# ReButton-ES2.net
KiCad netlist of a schematic drawn in EAGLE
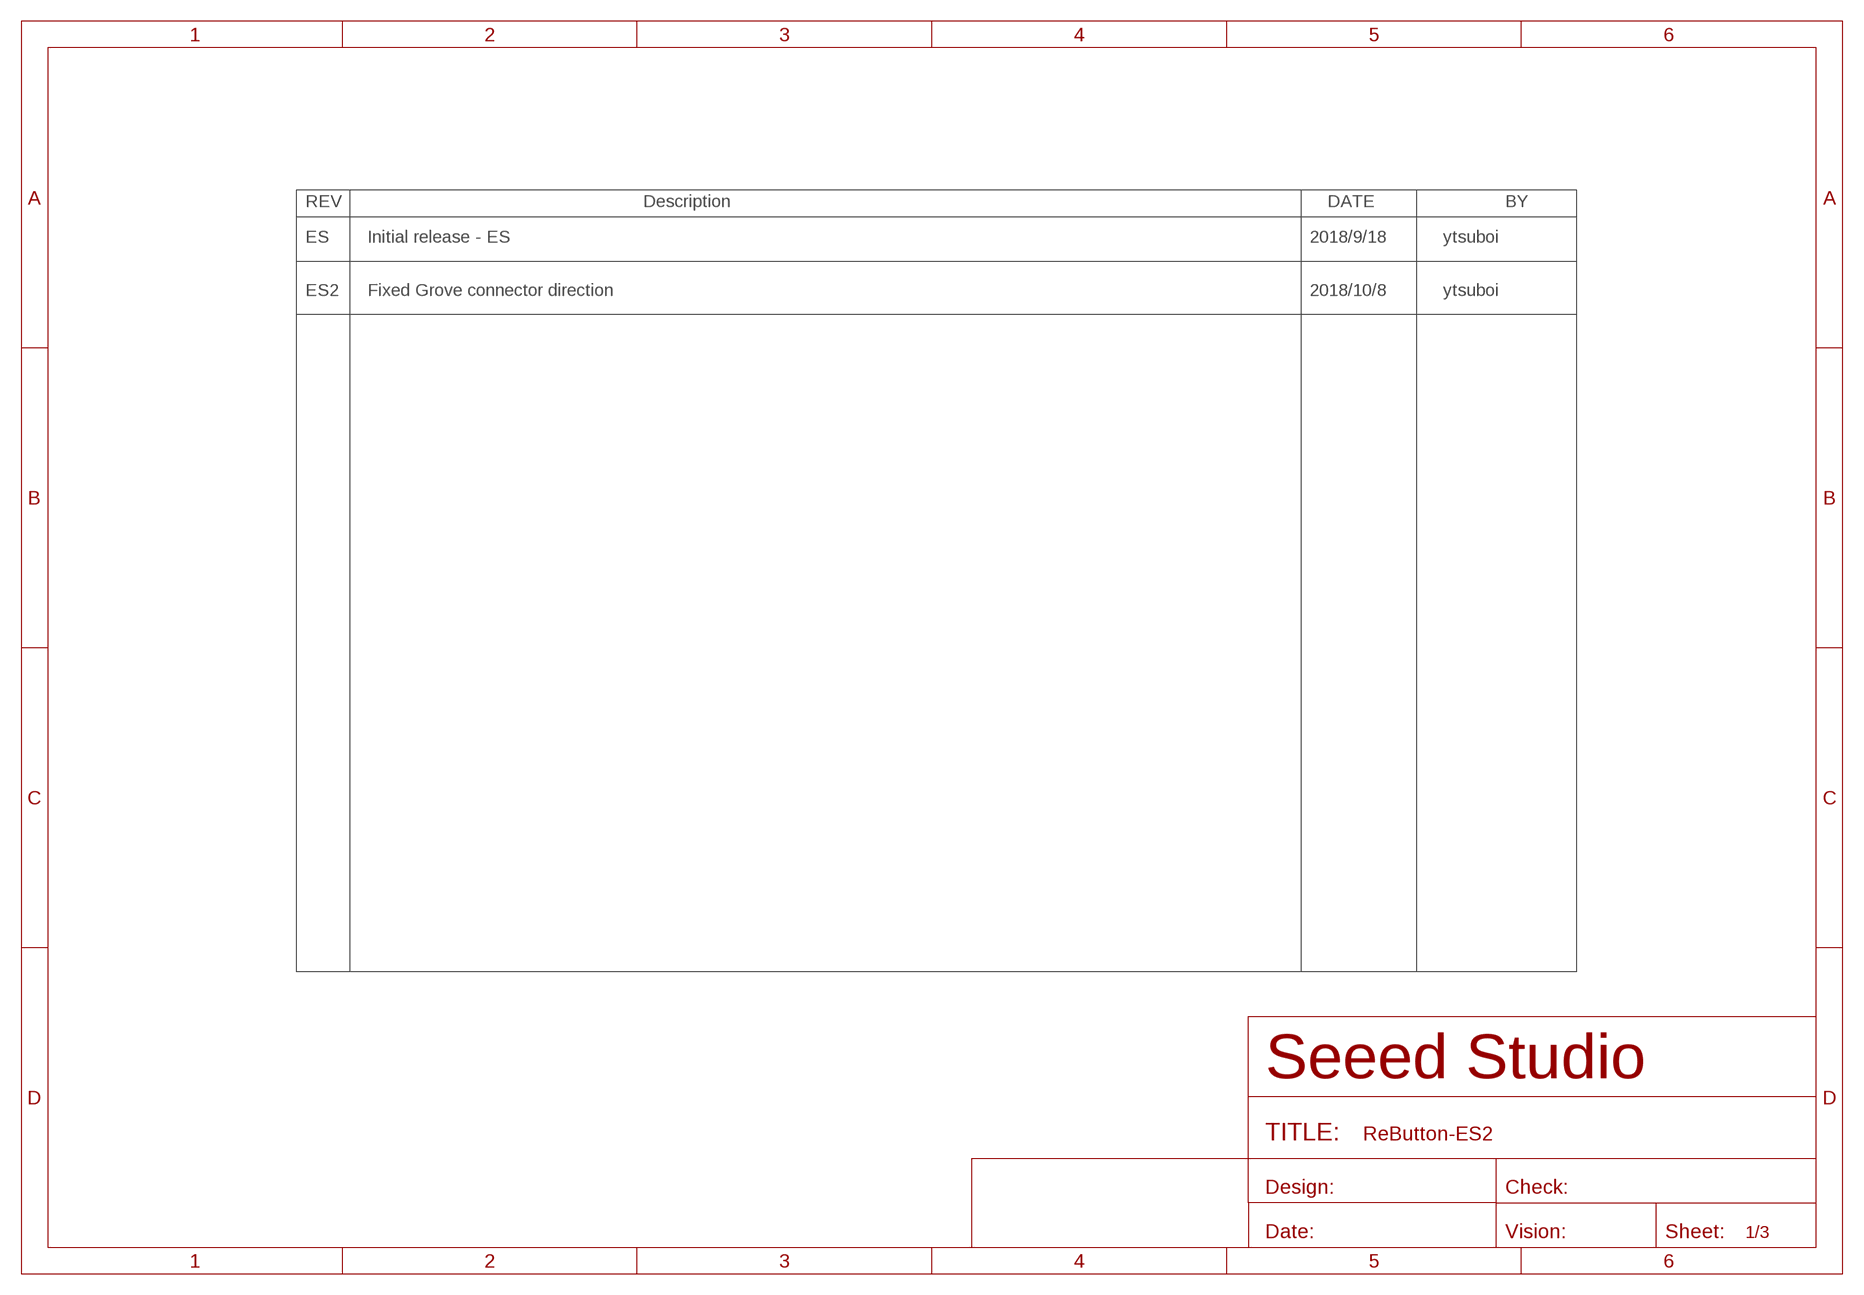
[diagram p0: schematic, sheet 1]
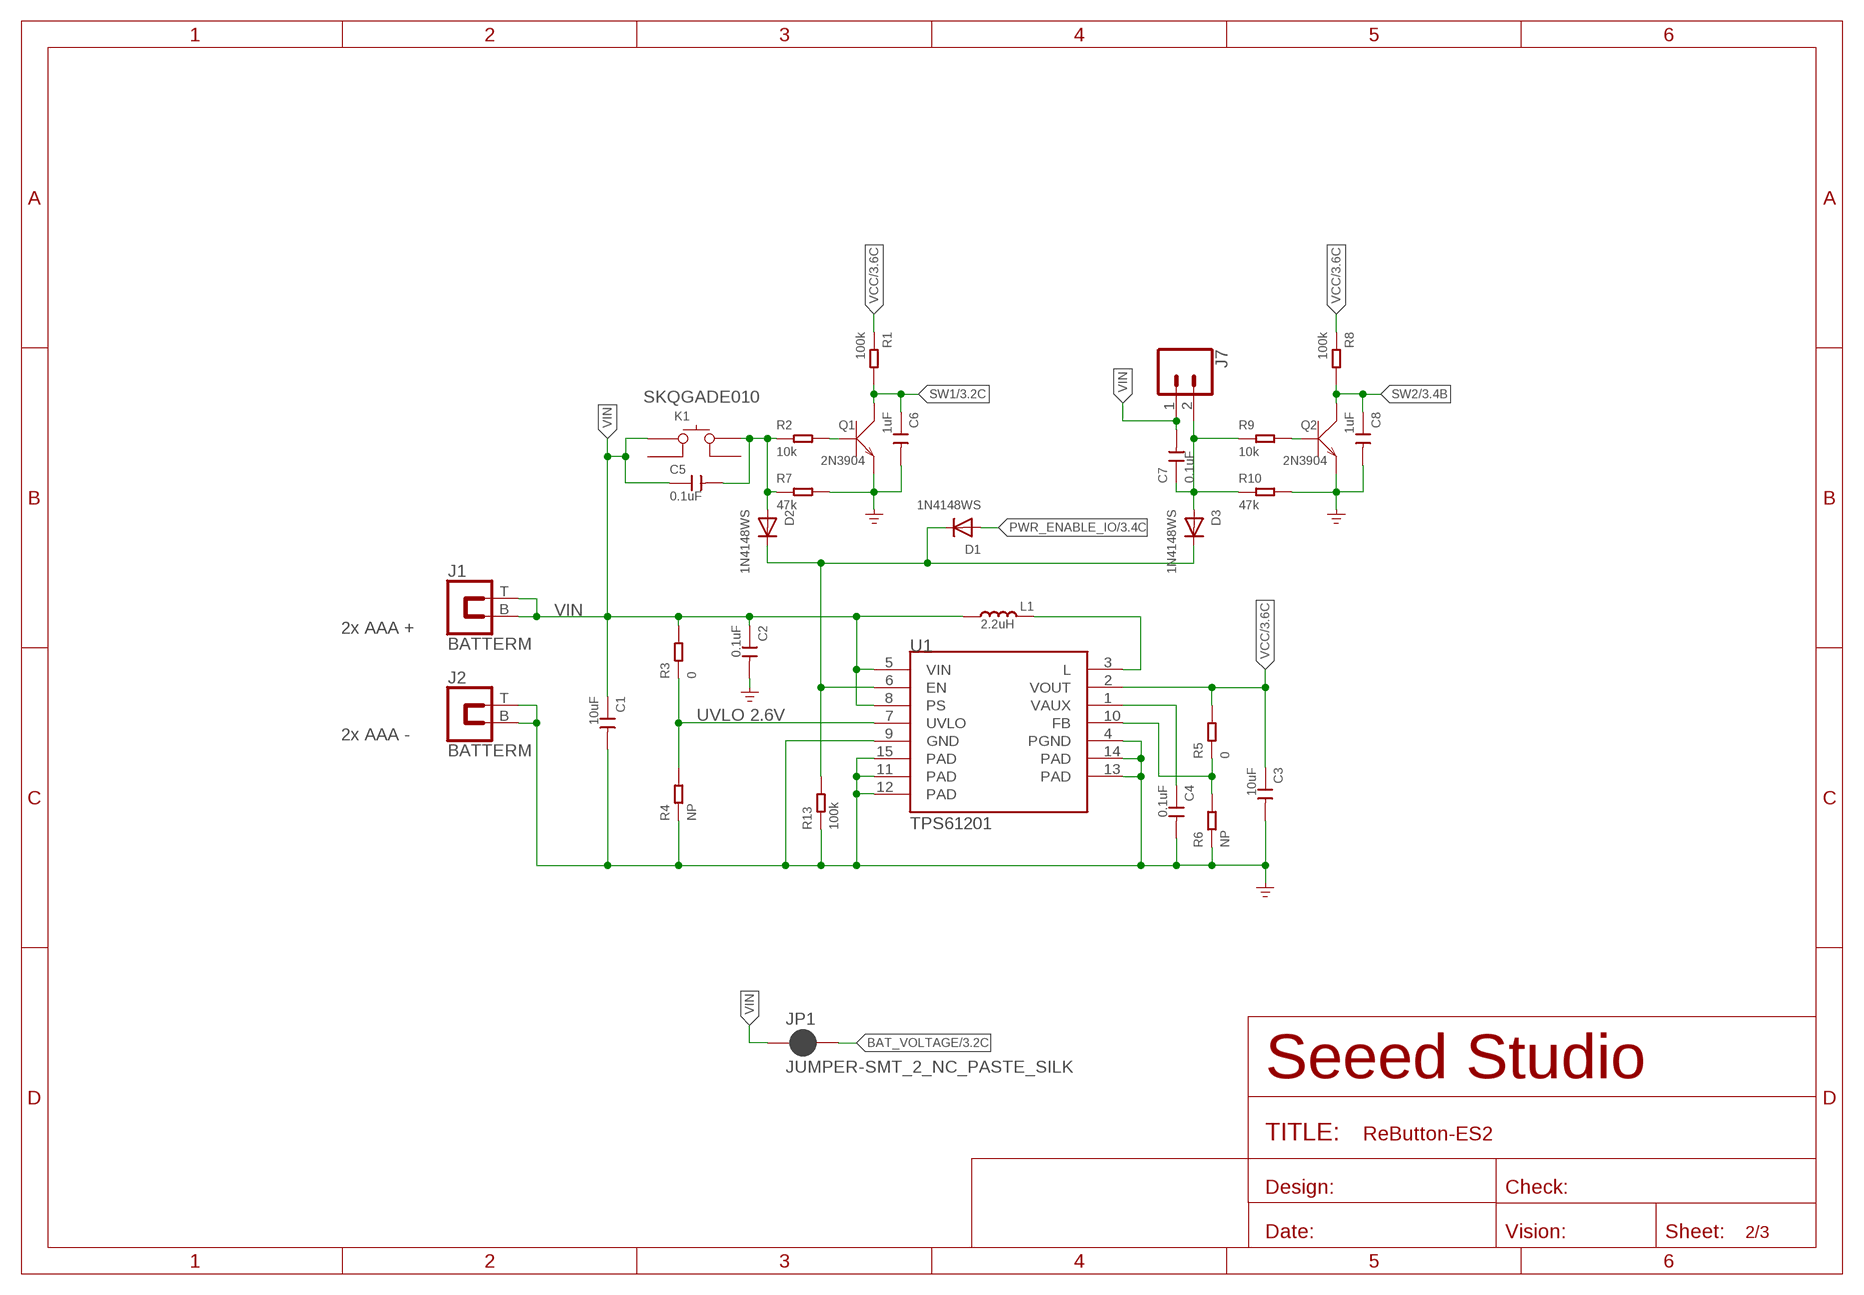
[diagram p1: schematic, sheet 2]
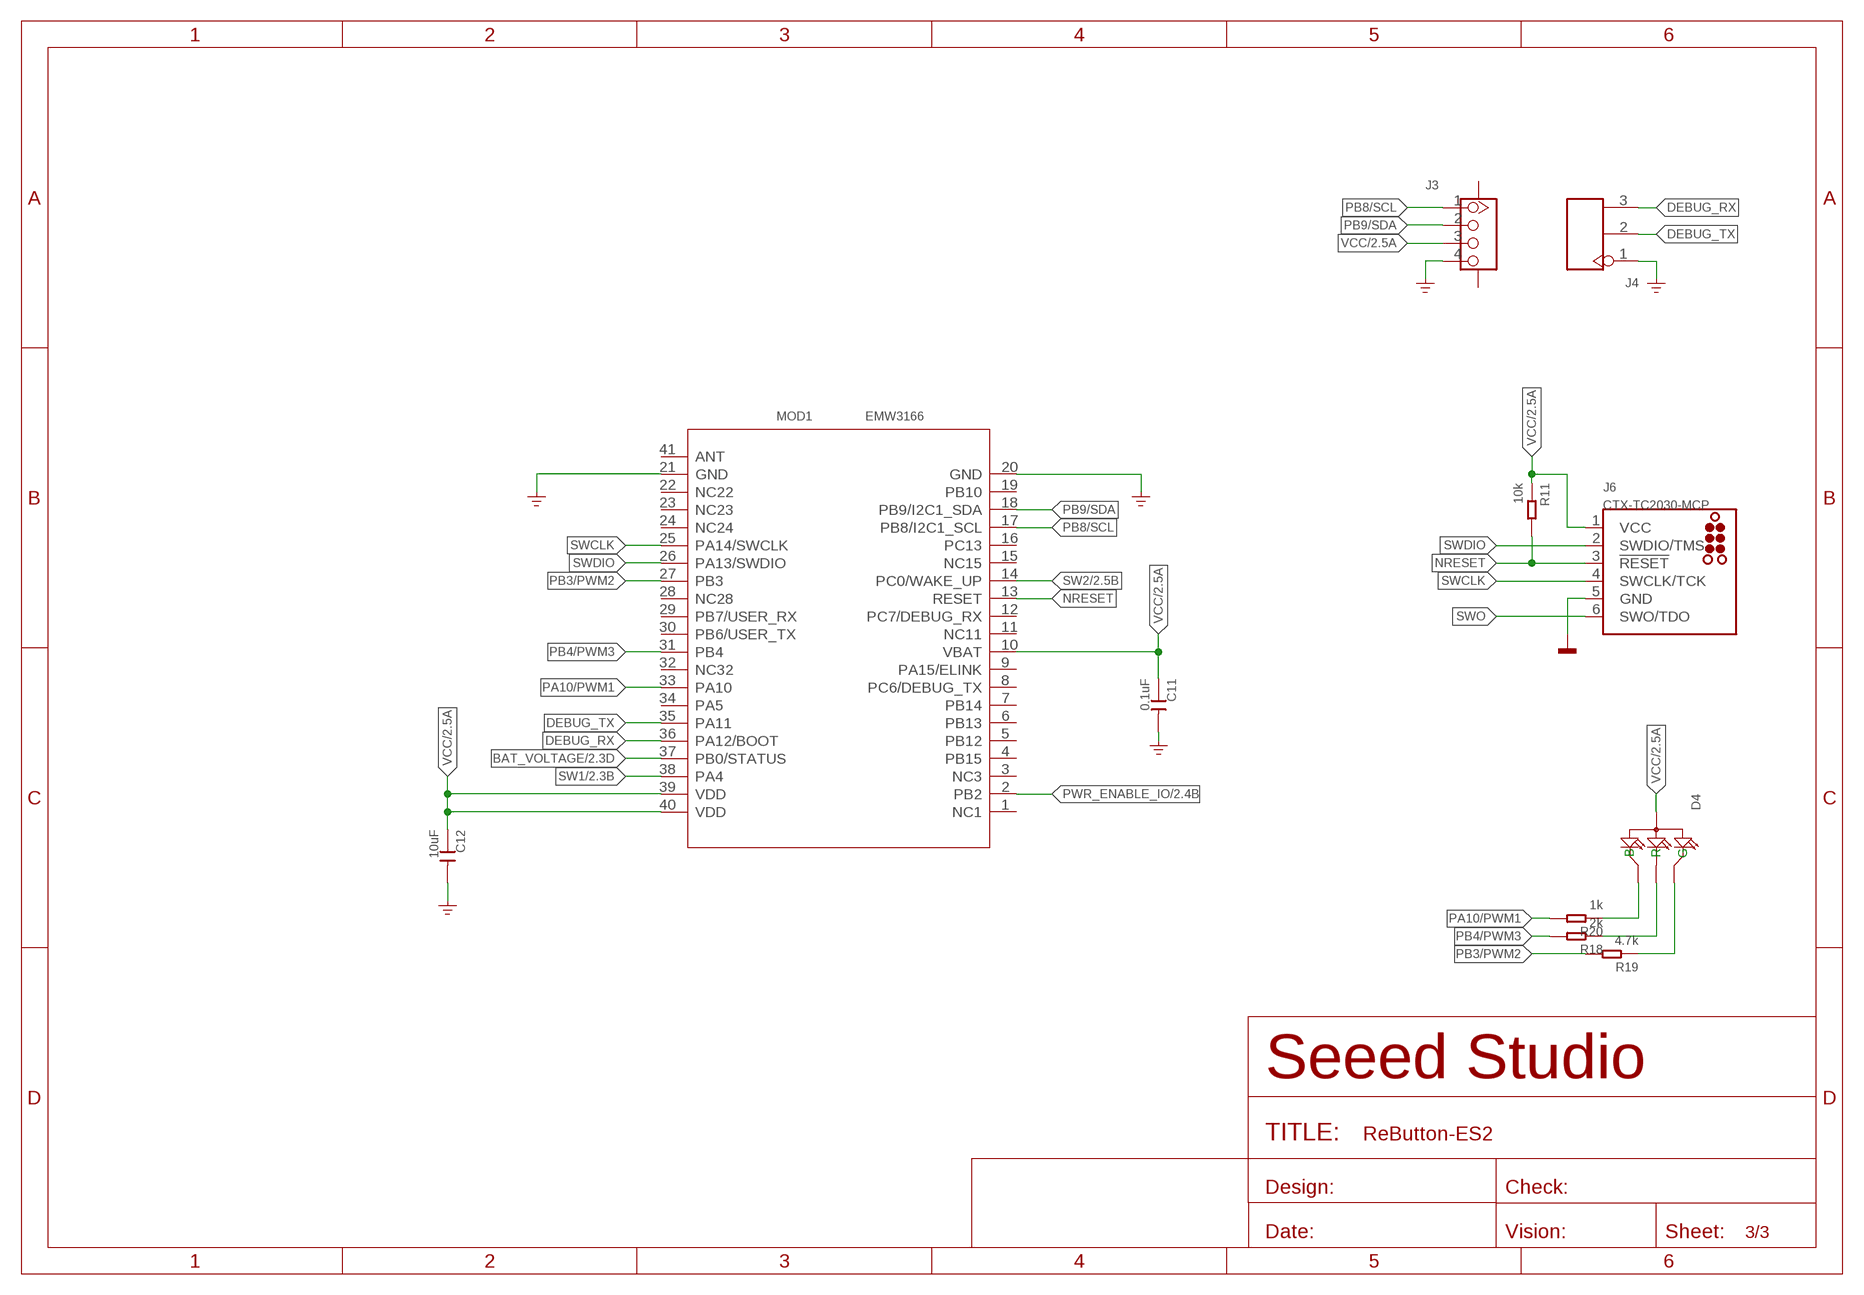
[diagram p2: schematic, sheet 3]

(export (version "E")
  (design (tool "Eeschema 10.0.6"))
  (components
    (comp (ref "C1")
      (value "10uF")
      (footprint "eagle-import:C0805")
      (libsource (lib "eagle-import") (part "CAP-0805"))
    )
    (comp (ref "C2")
      (value "0.1uF")
      (footprint "eagle-import:C0402")
      (libsource (lib "eagle-import") (part "CAP-0402"))
    )
    (comp (ref "C3")
      (value "10uF")
      (footprint "eagle-import:C0805")
      (libsource (lib "eagle-import") (part "CAP-0805"))
    )
    (comp (ref "C4")
      (value "0.1uF")
      (footprint "eagle-import:C0402")
      (libsource (lib "eagle-import") (part "CAP-0402"))
    )
    (comp (ref "C5")
      (value "0.1uF")
      (footprint "eagle-import:C0402")
      (libsource (lib "eagle-import") (part "CAP-0402"))
    )
    (comp (ref "C6")
      (value "1uF")
      (footprint "eagle-import:C0402")
      (libsource (lib "eagle-import") (part "CAP-0402"))
    )
    (comp (ref "C7")
      (value "0.1uF")
      (footprint "eagle-import:C0402")
      (libsource (lib "eagle-import") (part "CAP-0402"))
    )
    (comp (ref "C8")
      (value "1uF")
      (footprint "eagle-import:C0402")
      (libsource (lib "eagle-import") (part "CAP-0402"))
    )
    (comp (ref "D1")
      (value "1N4148WS")
      (footprint "eagle-import:SOD-323")
      (libsource (lib "eagle-import") (part "DIODESOD-323"))
    )
    (comp (ref "D2")
      (value "1N4148WS")
      (footprint "eagle-import:SOD-323")
      (libsource (lib "eagle-import") (part "DIODESOD-323"))
    )
    (comp (ref "D3")
      (value "1N4148WS")
      (footprint "eagle-import:SOD-323")
      (libsource (lib "eagle-import") (part "DIODESOD-323"))
    )
    (comp (ref "J1")
      (value "BATTERM")
      (footprint "eagle-import:BATTERM")
      (libsource (lib "eagle-import") (part "BATTERM"))
    )
    (comp (ref "J2")
      (value "BATTERM")
      (footprint "eagle-import:BATTERM")
      (libsource (lib "eagle-import") (part "BATTERM"))
    )
    (comp (ref "J7")
      (value "CONN_02LOCK")
      (footprint "eagle-import:1X02_LOCK")
      (libsource (lib "eagle-import") (part "CONN_02LOCK"))
    )
    (comp (ref "JP1")
      (value "JUMPER-SMT_2_NC_PASTE_SILK")
      (footprint "eagle-import:SMT-JUMPER_2_NC_PASTE_SILK")
      (libsource (lib "eagle-import") (part "JUMPER-SMT_2_NC_PASTE_SILK"))
    )
    (comp (ref "K1")
      (value "BUTTON-4P-6.2X6.2")
      (footprint "eagle-import:SW4-SMD-6.2X6.2MM")
      (libsource (lib "eagle-import") (part "BUTTON-4P-6.2X6.2"))
    )
    (comp (ref "L1")
      (value "2.2uH")
      (footprint "eagle-import:L3030-TAIYO-YUDEN-NR3012")
      (libsource (lib "eagle-import") (part "L-NR3012"))
    )
    (comp (ref "Q1")
      (value "2N3904")
      (footprint "eagle-import:SOT-23")
      (libsource (lib "eagle-import") (part "TRANSISTOR-NPN-SOT23"))
    )
    (comp (ref "Q2")
      (value "2N3904")
      (footprint "eagle-import:SOT-23")
      (libsource (lib "eagle-import") (part "TRANSISTOR-NPN-SOT23"))
    )
    (comp (ref "R1")
      (value "100k")
      (footprint "eagle-import:R0402")
      (libsource (lib "eagle-import") (part "RES-0402"))
    )
    (comp (ref "R2")
      (value "10k")
      (footprint "eagle-import:R0402")
      (libsource (lib "eagle-import") (part "RES-0402"))
    )
    (comp (ref "R3")
      (value "0")
      (footprint "eagle-import:R0402")
      (libsource (lib "eagle-import") (part "RES-0402"))
    )
    (comp (ref "R4")
      (value "NP")
      (footprint "eagle-import:R0402")
      (libsource (lib "eagle-import") (part "RES-0402"))
    )
    (comp (ref "R5")
      (value "0")
      (footprint "eagle-import:R0402")
      (libsource (lib "eagle-import") (part "RES-0402"))
    )
    (comp (ref "R6")
      (value "NP")
      (footprint "eagle-import:R0402")
      (libsource (lib "eagle-import") (part "RES-0402"))
    )
    (comp (ref "R7")
      (value "47k")
      (footprint "eagle-import:R0402")
      (libsource (lib "eagle-import") (part "RES-0402"))
    )
    (comp (ref "R8")
      (value "100k")
      (footprint "eagle-import:R0402")
      (libsource (lib "eagle-import") (part "RES-0402"))
    )
    (comp (ref "R9")
      (value "10k")
      (footprint "eagle-import:R0402")
      (libsource (lib "eagle-import") (part "RES-0402"))
    )
    (comp (ref "R10")
      (value "47k")
      (footprint "eagle-import:R0402")
      (libsource (lib "eagle-import") (part "RES-0402"))
    )
    (comp (ref "R13")
      (value "100k")
      (footprint "eagle-import:R0402")
      (libsource (lib "eagle-import") (part "RES-0402"))
    )
    (comp (ref "U1")
      (value "TPS61201")
      (footprint "eagle-import:QFN-10_PAD")
      (libsource (lib "eagle-import") (part "TPS61200"))
    )
    (comp (ref "C11")
      (value "0.1uF")
      (footprint "eagle-import:C0402")
      (libsource (lib "eagle-import") (part "CAP-0402"))
    )
    (comp (ref "C12")
      (value "10uF")
      (footprint "eagle-import:C0805")
      (libsource (lib "eagle-import") (part "CAP-0805"))
    )
    (comp (ref "D4")
      (value "LED-ARGB-4P-19-237")
      (footprint "eagle-import:LED4-1.6X1.6X0.35MM")
      (libsource (lib "eagle-import") (part "LED-ARGB-4P-19-237"))
    )
    (comp (ref "J3")
      (value "GROVE-CONNECTOR-SMD'DD'")
      (footprint "eagle-import:HW4-SMD-2.0")
      (libsource (lib "eagle-import") (part "GROVE-CONNECTOR-SMD'DD'"))
    )
    (comp (ref "J4")
      (value "HEADER-3P")
      (footprint "eagle-import:H3-2.3-65_35MIL")
      (libsource (lib "eagle-import") (part "HEADER-3P"))
    )
    (comp (ref "J6")
      (value "CTX-TC2030-MCP")
      (footprint "eagle-import:TC2030-MCP")
      (libsource (lib "eagle-import") (part "CTX-TC2030-MCP"))
    )
    (comp (ref "MOD1")
      (value "EMW3166")
      (footprint "eagle-import:MODULE-WIFI-EMW3166")
      (libsource (lib "eagle-import") (part "MODULE-WIFI-EMW3166"))
    )
    (comp (ref "R11")
      (value "10k")
      (footprint "eagle-import:R0402")
      (libsource (lib "eagle-import") (part "RES-0402"))
    )
    (comp (ref "R18")
      (value "2k")
      (footprint "eagle-import:R0402")
      (libsource (lib "eagle-import") (part "RES-0402"))
    )
    (comp (ref "R19")
      (value "4.7k")
      (footprint "eagle-import:R0402")
      (libsource (lib "eagle-import") (part "RES-0402"))
    )
    (comp (ref "R20")
      (value "1k")
      (footprint "eagle-import:R0402")
      (libsource (lib "eagle-import") (part "RES-0402"))
    )
  )
  (nets
    (net (code "1") (name "BAT_VOLTAGE") (class "Default")
      (node (ref "JP1") (pin "2") (pinfunction "2_2") (pintype "passive"))
      (node (ref "MOD1") (pin "37") (pinfunction "PB0/STATUS_37") (pintype "bidirectional"))
    )
    (net (code "2") (name "DEBUG_RX") (class "Default")
      (node (ref "J4") (pin "3") (pinfunction "P$3_3") (pintype "bidirectional"))
      (node (ref "MOD1") (pin "36") (pinfunction "PA12/BOOT_36") (pintype "bidirectional"))
    )
    (net (code "3") (name "DEBUG_TX") (class "Default")
      (node (ref "J4") (pin "2") (pinfunction "P$2_2") (pintype "bidirectional"))
      (node (ref "MOD1") (pin "35") (pinfunction "PA11_35") (pintype "bidirectional"))
    )
    (net (code "4") (name "GND") (class "Default")
      (node (ref "C1") (pin "2") (pinfunction "2_2") (pintype "passive"))
      (node (ref "C11") (pin "2") (pinfunction "2_2") (pintype "passive"))
      (node (ref "C12") (pin "2") (pinfunction "2_2") (pintype "passive"))
      (node (ref "C2") (pin "2") (pinfunction "2_2") (pintype "passive"))
      (node (ref "C3") (pin "2") (pinfunction "2_2") (pintype "passive"))
      (node (ref "C4") (pin "2") (pinfunction "2_2") (pintype "passive"))
      (node (ref "C6") (pin "2") (pinfunction "2_2") (pintype "passive"))
      (node (ref "C8") (pin "2") (pinfunction "2_2") (pintype "passive"))
      (node (ref "J2") (pin "B") (pinfunction "B_B") (pintype "passive"))
      (node (ref "J2") (pin "T") (pinfunction "T_T") (pintype "passive"))
      (node (ref "J3") (pin "4") (pinfunction "4_4") (pintype "bidirectional"))
      (node (ref "J4") (pin "1") (pinfunction "P$1_1") (pintype "bidirectional"))
      (node (ref "J6") (pin "5") (pinfunction "GND_5") (pintype "power_in"))
      (node (ref "MOD1") (pin "20") (pinfunction "GND_20") (pintype "power_in"))
      (node (ref "MOD1") (pin "21") (pinfunction "GND_21") (pintype "power_in"))
      (node (ref "Q1") (pin "2") (pinfunction "E_2") (pintype "passive"))
      (node (ref "Q2") (pin "2") (pinfunction "E_2") (pintype "passive"))
      (node (ref "R10") (pin "2") (pinfunction "2_2") (pintype "passive"))
      (node (ref "R13") (pin "1") (pinfunction "1_1") (pintype "passive"))
      (node (ref "R4") (pin "1") (pinfunction "1_1") (pintype "passive"))
      (node (ref "R6") (pin "1") (pinfunction "1_1") (pintype "passive"))
      (node (ref "R7") (pin "2") (pinfunction "2_2") (pintype "passive"))
      (node (ref "U1") (pin "11") (pinfunction "PAD_11") (pintype "power_in"))
      (node (ref "U1") (pin "12") (pinfunction "PAD_12") (pintype "power_in"))
      (node (ref "U1") (pin "13") (pinfunction "PAD_13") (pintype "power_in"))
      (node (ref "U1") (pin "14") (pinfunction "PAD_14") (pintype "power_in"))
      (node (ref "U1") (pin "15") (pinfunction "PAD_15") (pintype "power_in"))
      (node (ref "U1") (pin "4") (pinfunction "PGND_4") (pintype "power_in"))
      (node (ref "U1") (pin "9") (pinfunction "GND_9") (pintype "power_in"))
    )
    (net (code "5") (name "NRESET") (class "Default")
      (node (ref "J6") (pin "3") (pinfunction "~{RESET}_3") (pintype "bidirectional"))
      (node (ref "MOD1") (pin "13") (pinfunction "RESET_13") (pintype "bidirectional"))
      (node (ref "R11") (pin "2") (pinfunction "2_2") (pintype "passive"))
    )
    (net (code "6") (name "Net-(C7-Pad1)") (class "Default")
      (node (ref "C7") (pin "1") (pinfunction "1_1") (pintype "passive"))
      (node (ref "D3") (pin "A") (pinfunction "A_A") (pintype "passive"))
      (node (ref "J7") (pin "2") (pinfunction "2_2") (pintype "passive"))
      (node (ref "R10") (pin "1") (pinfunction "1_1") (pintype "passive"))
      (node (ref "R9") (pin "1") (pinfunction "1_1") (pintype "passive"))
    )
    (net (code "7") (name "Net-(D4-B)") (class "Default")
      (node (ref "D4") (pin "1") (pinfunction "B_1") (pintype "bidirectional"))
      (node (ref "R20") (pin "1") (pinfunction "1_1") (pintype "passive"))
    )
    (net (code "8") (name "Net-(D4-G)") (class "Default")
      (node (ref "D4") (pin "2") (pinfunction "G_2") (pintype "bidirectional"))
      (node (ref "R19") (pin "1") (pinfunction "1_1") (pintype "passive"))
    )
    (net (code "9") (name "Net-(D4-R)") (class "Default")
      (node (ref "D4") (pin "4") (pinfunction "R_4") (pintype "bidirectional"))
      (node (ref "R18") (pin "1") (pinfunction "1_1") (pintype "passive"))
    )
    (net (code "10") (name "Net-(K1-B0)") (class "Default")
      (node (ref "C5") (pin "2") (pinfunction "2_2") (pintype "passive"))
      (node (ref "D2") (pin "A") (pinfunction "A_A") (pintype "passive"))
      (node (ref "K1") (pin "2") (pinfunction "B0_2") (pintype "bidirectional"))
      (node (ref "R2") (pin "1") (pinfunction "1_1") (pintype "passive"))
      (node (ref "R7") (pin "1") (pinfunction "1_1") (pintype "passive"))
    )
    (net (code "11") (name "Net-(Q1-B)") (class "Default")
      (node (ref "Q1") (pin "1") (pinfunction "B_1") (pintype "passive"))
      (node (ref "R2") (pin "2") (pinfunction "2_2") (pintype "passive"))
    )
    (net (code "12") (name "Net-(Q2-B)") (class "Default")
      (node (ref "Q2") (pin "1") (pinfunction "B_1") (pintype "passive"))
      (node (ref "R9") (pin "2") (pinfunction "2_2") (pintype "passive"))
    )
    (net (code "13") (name "Net-(U1-EN)") (class "Default")
      (node (ref "D1") (pin "C") (pinfunction "C_C") (pintype "passive"))
      (node (ref "D2") (pin "C") (pinfunction "C_C") (pintype "passive"))
      (node (ref "D3") (pin "C") (pinfunction "C_C") (pintype "passive"))
      (node (ref "R13") (pin "2") (pinfunction "2_2") (pintype "passive"))
      (node (ref "U1") (pin "6") (pinfunction "EN_6") (pintype "input"))
    )
    (net (code "14") (name "Net-(U1-FB)") (class "Default")
      (node (ref "R5") (pin "1") (pinfunction "1_1") (pintype "passive"))
      (node (ref "R6") (pin "2") (pinfunction "2_2") (pintype "passive"))
      (node (ref "U1") (pin "10") (pinfunction "FB_10") (pintype "passive"))
    )
    (net (code "15") (name "Net-(U1-L)") (class "Default")
      (node (ref "L1") (pin "2") (pinfunction "2_2") (pintype "passive"))
      (node (ref "U1") (pin "3") (pinfunction "L_3") (pintype "passive"))
    )
    (net (code "16") (name "Net-(U1-UVLO)") (class "Default")
      (node (ref "R3") (pin "1") (pinfunction "1_1") (pintype "passive"))
      (node (ref "R4") (pin "2") (pinfunction "2_2") (pintype "passive"))
      (node (ref "U1") (pin "7") (pinfunction "UVLO_7") (pintype "passive"))
    )
    (net (code "17") (name "Net-(U1-VAUX)") (class "Default")
      (node (ref "C4") (pin "1") (pinfunction "1_1") (pintype "passive"))
      (node (ref "U1") (pin "1") (pinfunction "VAUX_1") (pintype "passive"))
    )
    (net (code "18") (name "PA10{slash}PWM1") (class "Default")
      (node (ref "MOD1") (pin "33") (pinfunction "PA10_33") (pintype "bidirectional"))
      (node (ref "R20") (pin "2") (pinfunction "2_2") (pintype "passive"))
    )
    (net (code "19") (name "PB3{slash}PWM2") (class "Default")
      (node (ref "MOD1") (pin "27") (pinfunction "PB3_27") (pintype "bidirectional"))
      (node (ref "R19") (pin "2") (pinfunction "2_2") (pintype "passive"))
    )
    (net (code "20") (name "PB4{slash}PWM3") (class "Default")
      (node (ref "MOD1") (pin "31") (pinfunction "PB4_31") (pintype "bidirectional"))
      (node (ref "R18") (pin "2") (pinfunction "2_2") (pintype "passive"))
    )
    (net (code "21") (name "PB8{slash}SCL") (class "Default")
      (node (ref "J3") (pin "1") (pinfunction "1_1") (pintype "bidirectional"))
      (node (ref "MOD1") (pin "17") (pinfunction "PB8/I2C1_SCL_17") (pintype "bidirectional"))
    )
    (net (code "22") (name "PB9{slash}SDA") (class "Default")
      (node (ref "J3") (pin "2") (pinfunction "2_2") (pintype "bidirectional"))
      (node (ref "MOD1") (pin "18") (pinfunction "PB9/I2C1_SDA_18") (pintype "bidirectional"))
    )
    (net (code "23") (name "PWR_ENABLE_IO") (class "Default")
      (node (ref "D1") (pin "A") (pinfunction "A_A") (pintype "passive"))
      (node (ref "MOD1") (pin "2") (pinfunction "PB2_2") (pintype "bidirectional"))
    )
    (net (code "24") (name "SW1") (class "Default")
      (node (ref "C6") (pin "1") (pinfunction "1_1") (pintype "passive"))
      (node (ref "MOD1") (pin "38") (pinfunction "PA4_38") (pintype "bidirectional"))
      (node (ref "Q1") (pin "3") (pinfunction "C_3") (pintype "passive"))
      (node (ref "R1") (pin "2") (pinfunction "2_2") (pintype "passive"))
    )
    (net (code "25") (name "SW2") (class "Default")
      (node (ref "C8") (pin "1") (pinfunction "1_1") (pintype "passive"))
      (node (ref "MOD1") (pin "14") (pinfunction "PC0/WAKE_UP_14") (pintype "bidirectional"))
      (node (ref "Q2") (pin "3") (pinfunction "C_3") (pintype "passive"))
      (node (ref "R8") (pin "2") (pinfunction "2_2") (pintype "passive"))
    )
    (net (code "26") (name "SWCLK") (class "Default")
      (node (ref "J6") (pin "4") (pinfunction "SWCLK/TCK_4") (pintype "bidirectional"))
      (node (ref "MOD1") (pin "25") (pinfunction "PA14/SWCLK_25") (pintype "bidirectional"))
    )
    (net (code "27") (name "SWDIO") (class "Default")
      (node (ref "J6") (pin "2") (pinfunction "SWDIO/TMS_2") (pintype "bidirectional"))
      (node (ref "MOD1") (pin "26") (pinfunction "PA13/SWDIO_26") (pintype "bidirectional"))
    )
    (net (code "28") (name "SWO") (class "Default")
      (node (ref "J6") (pin "6") (pinfunction "SWO/TDO_6") (pintype "bidirectional"))
    )
    (net (code "29") (name "VCC") (class "Default")
      (node (ref "C11") (pin "1") (pinfunction "1_1") (pintype "passive"))
      (node (ref "C12") (pin "1") (pinfunction "1_1") (pintype "passive"))
      (node (ref "C3") (pin "1") (pinfunction "1_1") (pintype "passive"))
      (node (ref "D4") (pin "3") (pinfunction "+_3") (pintype "bidirectional"))
      (node (ref "J3") (pin "3") (pinfunction "3_3") (pintype "bidirectional"))
      (node (ref "J6") (pin "1") (pinfunction "VCC_1") (pintype "power_in"))
      (node (ref "MOD1") (pin "10") (pinfunction "VBAT_10") (pintype "power_in"))
      (node (ref "MOD1") (pin "39") (pinfunction "VDD_39") (pintype "power_in"))
      (node (ref "MOD1") (pin "40") (pinfunction "VDD_40") (pintype "power_in"))
      (node (ref "R1") (pin "1") (pinfunction "1_1") (pintype "passive"))
      (node (ref "R11") (pin "1") (pinfunction "1_1") (pintype "passive"))
      (node (ref "R5") (pin "2") (pinfunction "2_2") (pintype "passive"))
      (node (ref "R8") (pin "1") (pinfunction "1_1") (pintype "passive"))
      (node (ref "U1") (pin "2") (pinfunction "VOUT_2") (pintype "passive"))
    )
    (net (code "30") (name "VIN") (class "Default")
      (node (ref "C1") (pin "1") (pinfunction "1_1") (pintype "passive"))
      (node (ref "C2") (pin "1") (pinfunction "1_1") (pintype "passive"))
      (node (ref "C5") (pin "1") (pinfunction "1_1") (pintype "passive"))
      (node (ref "C7") (pin "2") (pinfunction "2_2") (pintype "passive"))
      (node (ref "J1") (pin "B") (pinfunction "B_B") (pintype "passive"))
      (node (ref "J1") (pin "T") (pinfunction "T_T") (pintype "passive"))
      (node (ref "J7") (pin "1") (pinfunction "1_1") (pintype "passive"))
      (node (ref "JP1") (pin "1") (pinfunction "1_1") (pintype "passive"))
      (node (ref "K1") (pin "1") (pinfunction "A0_1") (pintype "bidirectional"))
      (node (ref "L1") (pin "1") (pinfunction "1_1") (pintype "passive"))
      (node (ref "R3") (pin "2") (pinfunction "2_2") (pintype "passive"))
      (node (ref "U1") (pin "5") (pinfunction "VIN_5") (pintype "power_in"))
      (node (ref "U1") (pin "8") (pinfunction "PS_8") (pintype "input"))
    )
    (net (code "31") (name "unconnected-(J3-PadSS1)") (class "Default")
      (node (ref "J3") (pin "SS1") (pinfunction "SS1_SS1") (pintype "bidirectional"))
    )
    (net (code "32") (name "unconnected-(J3-PadSS2)") (class "Default")
      (node (ref "J3") (pin "SS2") (pinfunction "SS2_SS2") (pintype "bidirectional"))
    )
    (net (code "33") (name "unconnected-(K1-A1-Pad4)") (class "Default")
      (node (ref "K1") (pin "4") (pinfunction "A1_4") (pintype "bidirectional"))
    )
    (net (code "34") (name "unconnected-(K1-B1-Pad3)") (class "Default")
      (node (ref "K1") (pin "3") (pinfunction "B1_3") (pintype "bidirectional"))
    )
    (net (code "35") (name "unconnected-(MOD1-ANT-Pad41)") (class "Default")
      (node (ref "MOD1") (pin "41") (pinfunction "ANT_41") (pintype "bidirectional"))
    )
    (net (code "36") (name "unconnected-(MOD1-NC1-Pad1)") (class "Default")
      (node (ref "MOD1") (pin "1") (pinfunction "NC1_1") (pintype "no_connect"))
    )
    (net (code "37") (name "unconnected-(MOD1-NC3-Pad3)") (class "Default")
      (node (ref "MOD1") (pin "3") (pinfunction "NC3_3") (pintype "no_connect"))
    )
    (net (code "38") (name "unconnected-(MOD1-NC11-Pad11)") (class "Default")
      (node (ref "MOD1") (pin "11") (pinfunction "NC11_11") (pintype "no_connect"))
    )
    (net (code "39") (name "unconnected-(MOD1-NC15-Pad15)") (class "Default")
      (node (ref "MOD1") (pin "15") (pinfunction "NC15_15") (pintype "no_connect"))
    )
    (net (code "40") (name "unconnected-(MOD1-NC22-Pad22)") (class "Default")
      (node (ref "MOD1") (pin "22") (pinfunction "NC22_22") (pintype "no_connect"))
    )
    (net (code "41") (name "unconnected-(MOD1-NC23-Pad23)") (class "Default")
      (node (ref "MOD1") (pin "23") (pinfunction "NC23_23") (pintype "no_connect"))
    )
    (net (code "42") (name "unconnected-(MOD1-NC24-Pad24)") (class "Default")
      (node (ref "MOD1") (pin "24") (pinfunction "NC24_24") (pintype "no_connect"))
    )
    (net (code "43") (name "unconnected-(MOD1-NC28-Pad28)") (class "Default")
      (node (ref "MOD1") (pin "28") (pinfunction "NC28_28") (pintype "no_connect"))
    )
    (net (code "44") (name "unconnected-(MOD1-NC32-Pad32)") (class "Default")
      (node (ref "MOD1") (pin "32") (pinfunction "NC32_32") (pintype "no_connect"))
    )
    (net (code "45") (name "unconnected-(MOD1-PA5-Pad34)") (class "Default")
      (node (ref "MOD1") (pin "34") (pinfunction "PA5_34") (pintype "bidirectional"))
    )
    (net (code "46") (name "unconnected-(MOD1-PA15{slash}ELINK-Pad9)") (class "Default")
      (node (ref "MOD1") (pin "9") (pinfunction "PA15/ELINK_9") (pintype "bidirectional"))
    )
    (net (code "47") (name "unconnected-(MOD1-PB6{slash}USER_TX-Pad30)") (class "Default")
      (node (ref "MOD1") (pin "30") (pinfunction "PB6/USER_TX_30") (pintype "bidirectional"))
    )
    (net (code "48") (name "unconnected-(MOD1-PB7{slash}USER_RX-Pad29)") (class "Default")
      (node (ref "MOD1") (pin "29") (pinfunction "PB7/USER_RX_29") (pintype "bidirectional"))
    )
    (net (code "49") (name "unconnected-(MOD1-PB10-Pad19)") (class "Default")
      (node (ref "MOD1") (pin "19") (pinfunction "PB10_19") (pintype "bidirectional"))
    )
    (net (code "50") (name "unconnected-(MOD1-PB12-Pad5)") (class "Default")
      (node (ref "MOD1") (pin "5") (pinfunction "PB12_5") (pintype "bidirectional"))
    )
    (net (code "51") (name "unconnected-(MOD1-PB13-Pad6)") (class "Default")
      (node (ref "MOD1") (pin "6") (pinfunction "PB13_6") (pintype "bidirectional"))
    )
    (net (code "52") (name "unconnected-(MOD1-PB14-Pad7)") (class "Default")
      (node (ref "MOD1") (pin "7") (pinfunction "PB14_7") (pintype "bidirectional"))
    )
    (net (code "53") (name "unconnected-(MOD1-PB15-Pad4)") (class "Default")
      (node (ref "MOD1") (pin "4") (pinfunction "PB15_4") (pintype "bidirectional"))
    )
    (net (code "54") (name "unconnected-(MOD1-PC6{slash}DEBUG_TX-Pad8)") (class "Default")
      (node (ref "MOD1") (pin "8") (pinfunction "PC6/DEBUG_TX_8") (pintype "bidirectional"))
    )
    (net (code "55") (name "unconnected-(MOD1-PC7{slash}DEBUG_RX-Pad12)") (class "Default")
      (node (ref "MOD1") (pin "12") (pinfunction "PC7/DEBUG_RX_12") (pintype "bidirectional"))
    )
    (net (code "56") (name "unconnected-(MOD1-PC13-Pad16)") (class "Default")
      (node (ref "MOD1") (pin "16") (pinfunction "PC13_16") (pintype "bidirectional"))
    )
  )
)
